# sch_maV1.net
KiCad netlist of a schematic drawn in Altium Designer
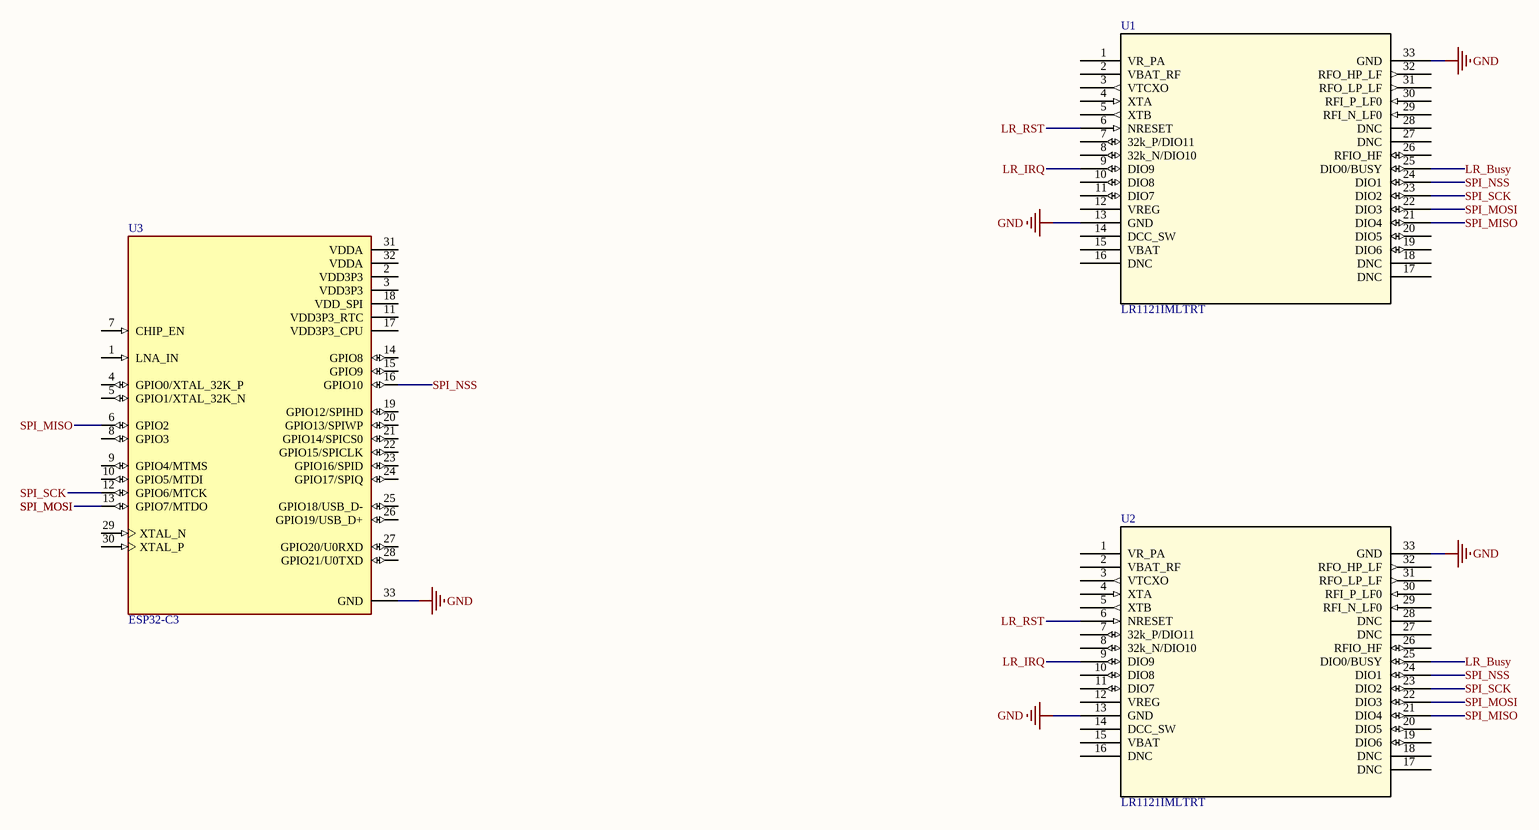
[diagram p0: schémaV1.SchDoc]

(export (version "E")
  (design (tool "Eeschema 10.0.6"))
  (components
    (comp (ref "U1")
      (value "LR1121IMLTRT")
      (footprint "QFN32_5X5_MLP_SEM")
      (description "Description")
      (fields (field (name "COPYRIGHT") "Copyright (C) 2025 Ultra Librarian. All rights reserved."))
      (libsource (lib "LR1121IMLTRT") (part "LR1121IMLTRT"))
    )
    (comp (ref "U2")
      (value "LR1121IMLTRT")
      (footprint "QFN32_5X5_MLP_SEM")
      (description "Description")
      (fields (field (name "COPYRIGHT") "Copyright (C) 2025 Ultra Librarian. All rights reserved."))
      (libsource (lib "LR1121IMLTRT") (part "LR1121IMLTRT"))
    )
    (comp (ref "U3")
      (value "ESP32-C3")
      (footprint "QFN50P500X500X90-33N")
      (fields (field (name "MF") "Espressif Systems"))
      (libsource (lib "ESP32-C3") (part "ESP32-C3"))
    )
  )
  (nets
    (net (code "1") (name "/LR_Busy") (class "Default")
      (node (ref "U1") (pin "25") (pinfunction "DIO0/BUSY_25") (pintype "bidirectional"))
      (node (ref "U2") (pin "25") (pinfunction "DIO0/BUSY_25") (pintype "bidirectional"))
    )
    (net (code "2") (name "/LR_IRQ") (class "Default")
      (node (ref "U1") (pin "9") (pinfunction "DIO9_9") (pintype "bidirectional"))
      (node (ref "U2") (pin "9") (pinfunction "DIO9_9") (pintype "bidirectional"))
    )
    (net (code "3") (name "/LR_RST") (class "Default")
      (node (ref "U1") (pin "6") (pinfunction "NRESET_6") (pintype "input"))
      (node (ref "U2") (pin "6") (pinfunction "NRESET_6") (pintype "input"))
    )
    (net (code "4") (name "/SPI_MISO") (class "Default")
      (node (ref "U1") (pin "21") (pinfunction "DIO4_21") (pintype "bidirectional"))
      (node (ref "U2") (pin "21") (pinfunction "DIO4_21") (pintype "bidirectional"))
      (node (ref "U3") (pin "6") (pinfunction "GPIO2_6") (pintype "bidirectional"))
    )
    (net (code "5") (name "/SPI_MOSI") (class "Default")
      (node (ref "U1") (pin "22") (pinfunction "DIO3_22") (pintype "bidirectional"))
      (node (ref "U2") (pin "22") (pinfunction "DIO3_22") (pintype "bidirectional"))
      (node (ref "U3") (pin "13") (pinfunction "GPIO7/MTDO_13") (pintype "bidirectional"))
    )
    (net (code "6") (name "/SPI_NSS") (class "Default")
      (node (ref "U1") (pin "24") (pinfunction "DIO1_24") (pintype "bidirectional"))
      (node (ref "U2") (pin "24") (pinfunction "DIO1_24") (pintype "bidirectional"))
      (node (ref "U3") (pin "16") (pinfunction "GPIO10_16") (pintype "bidirectional"))
    )
    (net (code "7") (name "/SPI_SCK") (class "Default")
      (node (ref "U1") (pin "23") (pinfunction "DIO2_23") (pintype "bidirectional"))
      (node (ref "U2") (pin "23") (pinfunction "DIO2_23") (pintype "bidirectional"))
      (node (ref "U3") (pin "12") (pinfunction "GPIO6/MTCK_12") (pintype "bidirectional"))
    )
    (net (code "8") (name "GND") (class "Default")
      (node (ref "U1") (pin "13") (pinfunction "GND_13") (pintype "power_in"))
      (node (ref "U1") (pin "33") (pinfunction "GND_33") (pintype "power_in"))
      (node (ref "U2") (pin "13") (pinfunction "GND_13") (pintype "power_in"))
      (node (ref "U2") (pin "33") (pinfunction "GND_33") (pintype "power_in"))
      (node (ref "U3") (pin "33") (pinfunction "GND_33") (pintype "power_in"))
    )
    (net (code "9") (name "unconnected-(U1-32k_N{slash}DIO10-Pad8)") (class "Default")
      (node (ref "U1") (pin "8") (pinfunction "32k_N/DIO10_8") (pintype "bidirectional"))
    )
    (net (code "10") (name "unconnected-(U1-32k_P{slash}DIO11-Pad7)") (class "Default")
      (node (ref "U1") (pin "7") (pinfunction "32k_P/DIO11_7") (pintype "bidirectional"))
    )
    (net (code "11") (name "unconnected-(U1-DCC_SW-Pad14)") (class "Default")
      (node (ref "U1") (pin "14") (pinfunction "DCC_SW_14") (pintype "power_in"))
    )
    (net (code "12") (name "unconnected-(U1-DIO5-Pad20)") (class "Default")
      (node (ref "U1") (pin "20") (pinfunction "DIO5_20") (pintype "bidirectional"))
    )
    (net (code "13") (name "unconnected-(U1-DIO6-Pad19)") (class "Default")
      (node (ref "U1") (pin "19") (pinfunction "DIO6_19") (pintype "bidirectional"))
    )
    (net (code "14") (name "unconnected-(U1-DIO7-Pad11)") (class "Default")
      (node (ref "U1") (pin "11") (pinfunction "DIO7_11") (pintype "bidirectional"))
    )
    (net (code "15") (name "unconnected-(U1-DIO8-Pad10)") (class "Default")
      (node (ref "U1") (pin "10") (pinfunction "DIO8_10") (pintype "bidirectional"))
    )
    (net (code "16") (name "unconnected-(U1-DNC-Pad16)") (class "Default")
      (node (ref "U1") (pin "16") (pinfunction "DNC_16") (pintype "passive"))
    )
    (net (code "17") (name "unconnected-(U1-DNC-Pad17)") (class "Default")
      (node (ref "U1") (pin "17") (pinfunction "DNC_17") (pintype "passive"))
    )
    (net (code "18") (name "unconnected-(U1-DNC-Pad18)") (class "Default")
      (node (ref "U1") (pin "18") (pinfunction "DNC_18") (pintype "passive"))
    )
    (net (code "19") (name "unconnected-(U1-DNC-Pad27)") (class "Default")
      (node (ref "U1") (pin "27") (pinfunction "DNC_27") (pintype "passive"))
    )
    (net (code "20") (name "unconnected-(U1-DNC-Pad28)") (class "Default")
      (node (ref "U1") (pin "28") (pinfunction "DNC_28") (pintype "passive"))
    )
    (net (code "21") (name "unconnected-(U1-RFIO_HF-Pad26)") (class "Default")
      (node (ref "U1") (pin "26") (pinfunction "RFIO_HF_26") (pintype "bidirectional"))
    )
    (net (code "22") (name "unconnected-(U1-RFI_N_LF0-Pad29)") (class "Default")
      (node (ref "U1") (pin "29") (pinfunction "RFI_N_LF0_29") (pintype "input"))
    )
    (net (code "23") (name "unconnected-(U1-RFI_P_LF0-Pad30)") (class "Default")
      (node (ref "U1") (pin "30") (pinfunction "RFI_P_LF0_30") (pintype "input"))
    )
    (net (code "24") (name "unconnected-(U1-RFO_HP_LF-Pad32)") (class "Default")
      (node (ref "U1") (pin "32") (pinfunction "RFO_HP_LF_32") (pintype "output"))
    )
    (net (code "25") (name "unconnected-(U1-RFO_LP_LF-Pad31)") (class "Default")
      (node (ref "U1") (pin "31") (pinfunction "RFO_LP_LF_31") (pintype "output"))
    )
    (net (code "26") (name "unconnected-(U1-VBAT-Pad15)") (class "Default")
      (node (ref "U1") (pin "15") (pinfunction "VBAT_15") (pintype "power_in"))
    )
    (net (code "27") (name "unconnected-(U1-VBAT_RF-Pad2)") (class "Default")
      (node (ref "U1") (pin "2") (pinfunction "VBAT_RF_2") (pintype "power_in"))
    )
    (net (code "28") (name "unconnected-(U1-VREG-Pad12)") (class "Default")
      (node (ref "U1") (pin "12") (pinfunction "VREG_12") (pintype "power_in"))
    )
    (net (code "29") (name "unconnected-(U1-VR_PA-Pad1)") (class "Default")
      (node (ref "U1") (pin "1") (pinfunction "VR_PA_1") (pintype "power_in"))
    )
    (net (code "30") (name "unconnected-(U1-VTCXO-Pad3)") (class "Default")
      (node (ref "U1") (pin "3") (pinfunction "VTCXO_3") (pintype "output"))
    )
    (net (code "31") (name "unconnected-(U1-XTA-Pad4)") (class "Default")
      (node (ref "U1") (pin "4") (pinfunction "XTA_4") (pintype "input"))
    )
    (net (code "32") (name "unconnected-(U1-XTB-Pad5)") (class "Default")
      (node (ref "U1") (pin "5") (pinfunction "XTB_5") (pintype "output"))
    )
    (net (code "33") (name "unconnected-(U2-32k_N{slash}DIO10-Pad8)") (class "Default")
      (node (ref "U2") (pin "8") (pinfunction "32k_N/DIO10_8") (pintype "bidirectional"))
    )
    (net (code "34") (name "unconnected-(U2-32k_P{slash}DIO11-Pad7)") (class "Default")
      (node (ref "U2") (pin "7") (pinfunction "32k_P/DIO11_7") (pintype "bidirectional"))
    )
    (net (code "35") (name "unconnected-(U2-DCC_SW-Pad14)") (class "Default")
      (node (ref "U2") (pin "14") (pinfunction "DCC_SW_14") (pintype "power_in"))
    )
    (net (code "36") (name "unconnected-(U2-DIO5-Pad20)") (class "Default")
      (node (ref "U2") (pin "20") (pinfunction "DIO5_20") (pintype "bidirectional"))
    )
    (net (code "37") (name "unconnected-(U2-DIO6-Pad19)") (class "Default")
      (node (ref "U2") (pin "19") (pinfunction "DIO6_19") (pintype "bidirectional"))
    )
    (net (code "38") (name "unconnected-(U2-DIO7-Pad11)") (class "Default")
      (node (ref "U2") (pin "11") (pinfunction "DIO7_11") (pintype "bidirectional"))
    )
    (net (code "39") (name "unconnected-(U2-DIO8-Pad10)") (class "Default")
      (node (ref "U2") (pin "10") (pinfunction "DIO8_10") (pintype "bidirectional"))
    )
    (net (code "40") (name "unconnected-(U2-DNC-Pad16)") (class "Default")
      (node (ref "U2") (pin "16") (pinfunction "DNC_16") (pintype "passive"))
    )
    (net (code "41") (name "unconnected-(U2-DNC-Pad17)") (class "Default")
      (node (ref "U2") (pin "17") (pinfunction "DNC_17") (pintype "passive"))
    )
    (net (code "42") (name "unconnected-(U2-DNC-Pad18)") (class "Default")
      (node (ref "U2") (pin "18") (pinfunction "DNC_18") (pintype "passive"))
    )
    (net (code "43") (name "unconnected-(U2-DNC-Pad27)") (class "Default")
      (node (ref "U2") (pin "27") (pinfunction "DNC_27") (pintype "passive"))
    )
    (net (code "44") (name "unconnected-(U2-DNC-Pad28)") (class "Default")
      (node (ref "U2") (pin "28") (pinfunction "DNC_28") (pintype "passive"))
    )
    (net (code "45") (name "unconnected-(U2-RFIO_HF-Pad26)") (class "Default")
      (node (ref "U2") (pin "26") (pinfunction "RFIO_HF_26") (pintype "bidirectional"))
    )
    (net (code "46") (name "unconnected-(U2-RFI_N_LF0-Pad29)") (class "Default")
      (node (ref "U2") (pin "29") (pinfunction "RFI_N_LF0_29") (pintype "input"))
    )
    (net (code "47") (name "unconnected-(U2-RFI_P_LF0-Pad30)") (class "Default")
      (node (ref "U2") (pin "30") (pinfunction "RFI_P_LF0_30") (pintype "input"))
    )
    (net (code "48") (name "unconnected-(U2-RFO_HP_LF-Pad32)") (class "Default")
      (node (ref "U2") (pin "32") (pinfunction "RFO_HP_LF_32") (pintype "output"))
    )
    (net (code "49") (name "unconnected-(U2-RFO_LP_LF-Pad31)") (class "Default")
      (node (ref "U2") (pin "31") (pinfunction "RFO_LP_LF_31") (pintype "output"))
    )
    (net (code "50") (name "unconnected-(U2-VBAT-Pad15)") (class "Default")
      (node (ref "U2") (pin "15") (pinfunction "VBAT_15") (pintype "power_in"))
    )
    (net (code "51") (name "unconnected-(U2-VBAT_RF-Pad2)") (class "Default")
      (node (ref "U2") (pin "2") (pinfunction "VBAT_RF_2") (pintype "power_in"))
    )
    (net (code "52") (name "unconnected-(U2-VREG-Pad12)") (class "Default")
      (node (ref "U2") (pin "12") (pinfunction "VREG_12") (pintype "power_in"))
    )
    (net (code "53") (name "unconnected-(U2-VR_PA-Pad1)") (class "Default")
      (node (ref "U2") (pin "1") (pinfunction "VR_PA_1") (pintype "power_in"))
    )
    (net (code "54") (name "unconnected-(U2-VTCXO-Pad3)") (class "Default")
      (node (ref "U2") (pin "3") (pinfunction "VTCXO_3") (pintype "output"))
    )
    (net (code "55") (name "unconnected-(U2-XTA-Pad4)") (class "Default")
      (node (ref "U2") (pin "4") (pinfunction "XTA_4") (pintype "input"))
    )
    (net (code "56") (name "unconnected-(U2-XTB-Pad5)") (class "Default")
      (node (ref "U2") (pin "5") (pinfunction "XTB_5") (pintype "output"))
    )
    (net (code "57") (name "unconnected-(U3-CHIP_EN-Pad7)") (class "Default")
      (node (ref "U3") (pin "7") (pinfunction "CHIP_EN_7") (pintype "input"))
    )
    (net (code "58") (name "unconnected-(U3-GPIO0{slash}XTAL_32K_P-Pad4)") (class "Default")
      (node (ref "U3") (pin "4") (pinfunction "GPIO0/XTAL_32K_P_4") (pintype "bidirectional"))
    )
    (net (code "59") (name "unconnected-(U3-GPIO1{slash}XTAL_32K_N-Pad5)") (class "Default")
      (node (ref "U3") (pin "5") (pinfunction "GPIO1/XTAL_32K_N_5") (pintype "bidirectional"))
    )
    (net (code "60") (name "unconnected-(U3-GPIO3-Pad8)") (class "Default")
      (node (ref "U3") (pin "8") (pinfunction "GPIO3_8") (pintype "bidirectional"))
    )
    (net (code "61") (name "unconnected-(U3-GPIO4{slash}MTMS-Pad9)") (class "Default")
      (node (ref "U3") (pin "9") (pinfunction "GPIO4/MTMS_9") (pintype "bidirectional"))
    )
    (net (code "62") (name "unconnected-(U3-GPIO5{slash}MTDI-Pad10)") (class "Default")
      (node (ref "U3") (pin "10") (pinfunction "GPIO5/MTDI_10") (pintype "bidirectional"))
    )
    (net (code "63") (name "unconnected-(U3-GPIO8-Pad14)") (class "Default")
      (node (ref "U3") (pin "14") (pinfunction "GPIO8_14") (pintype "bidirectional"))
    )
    (net (code "64") (name "unconnected-(U3-GPIO9-Pad15)") (class "Default")
      (node (ref "U3") (pin "15") (pinfunction "GPIO9_15") (pintype "bidirectional"))
    )
    (net (code "65") (name "unconnected-(U3-GPIO12{slash}SPIHD-Pad19)") (class "Default")
      (node (ref "U3") (pin "19") (pinfunction "GPIO12/SPIHD_19") (pintype "bidirectional"))
    )
    (net (code "66") (name "unconnected-(U3-GPIO13{slash}SPIWP-Pad20)") (class "Default")
      (node (ref "U3") (pin "20") (pinfunction "GPIO13/SPIWP_20") (pintype "bidirectional"))
    )
    (net (code "67") (name "unconnected-(U3-GPIO14{slash}SPICS0-Pad21)") (class "Default")
      (node (ref "U3") (pin "21") (pinfunction "GPIO14/SPICS0_21") (pintype "bidirectional"))
    )
    (net (code "68") (name "unconnected-(U3-GPIO15{slash}SPICLK-Pad22)") (class "Default")
      (node (ref "U3") (pin "22") (pinfunction "GPIO15/SPICLK_22") (pintype "bidirectional"))
    )
    (net (code "69") (name "unconnected-(U3-GPIO16{slash}SPID-Pad23)") (class "Default")
      (node (ref "U3") (pin "23") (pinfunction "GPIO16/SPID_23") (pintype "bidirectional"))
    )
    (net (code "70") (name "unconnected-(U3-GPIO17{slash}SPIQ-Pad24)") (class "Default")
      (node (ref "U3") (pin "24") (pinfunction "GPIO17/SPIQ_24") (pintype "bidirectional"))
    )
    (net (code "71") (name "unconnected-(U3-GPIO18{slash}USB_D--Pad25)") (class "Default")
      (node (ref "U3") (pin "25") (pinfunction "GPIO18/USB_D-_25") (pintype "bidirectional"))
    )
    (net (code "72") (name "unconnected-(U3-GPIO19{slash}USB_D+-Pad26)") (class "Default")
      (node (ref "U3") (pin "26") (pinfunction "GPIO19/USB_D+_26") (pintype "bidirectional"))
    )
    (net (code "73") (name "unconnected-(U3-GPIO20{slash}U0RXD-Pad27)") (class "Default")
      (node (ref "U3") (pin "27") (pinfunction "GPIO20/U0RXD_27") (pintype "bidirectional"))
    )
    (net (code "74") (name "unconnected-(U3-GPIO21{slash}U0TXD-Pad28)") (class "Default")
      (node (ref "U3") (pin "28") (pinfunction "GPIO21/U0TXD_28") (pintype "bidirectional"))
    )
    (net (code "75") (name "unconnected-(U3-LNA_IN-Pad1)") (class "Default")
      (node (ref "U3") (pin "1") (pinfunction "LNA_IN_1") (pintype "input"))
    )
    (net (code "76") (name "unconnected-(U3-VDD3P3-Pad2)") (class "Default")
      (node (ref "U3") (pin "2") (pinfunction "VDD3P3_2") (pintype "power_in"))
    )
    (net (code "77") (name "unconnected-(U3-VDD3P3-Pad3)") (class "Default")
      (node (ref "U3") (pin "3") (pinfunction "VDD3P3_3") (pintype "power_in"))
    )
    (net (code "78") (name "unconnected-(U3-VDD3P3_CPU-Pad17)") (class "Default")
      (node (ref "U3") (pin "17") (pinfunction "VDD3P3_CPU_17") (pintype "power_in"))
    )
    (net (code "79") (name "unconnected-(U3-VDD3P3_RTC-Pad11)") (class "Default")
      (node (ref "U3") (pin "11") (pinfunction "VDD3P3_RTC_11") (pintype "power_in"))
    )
    (net (code "80") (name "unconnected-(U3-VDDA-Pad31)") (class "Default")
      (node (ref "U3") (pin "31") (pinfunction "VDDA_31") (pintype "power_in"))
    )
    (net (code "81") (name "unconnected-(U3-VDDA-Pad32)") (class "Default")
      (node (ref "U3") (pin "32") (pinfunction "VDDA_32") (pintype "power_in"))
    )
    (net (code "82") (name "unconnected-(U3-VDD_SPI-Pad18)") (class "Default")
      (node (ref "U3") (pin "18") (pinfunction "VDD_SPI_18") (pintype "power_in"))
    )
    (net (code "83") (name "unconnected-(U3-XTAL_N-Pad29)") (class "Default")
      (node (ref "U3") (pin "29") (pinfunction "XTAL_N_29") (pintype "input"))
    )
    (net (code "84") (name "unconnected-(U3-XTAL_P-Pad30)") (class "Default")
      (node (ref "U3") (pin "30") (pinfunction "XTAL_P_30") (pintype "input"))
    )
  )
)
